# DE-230724.net
KiCad netlist of a schematic drawn in Altium Designer
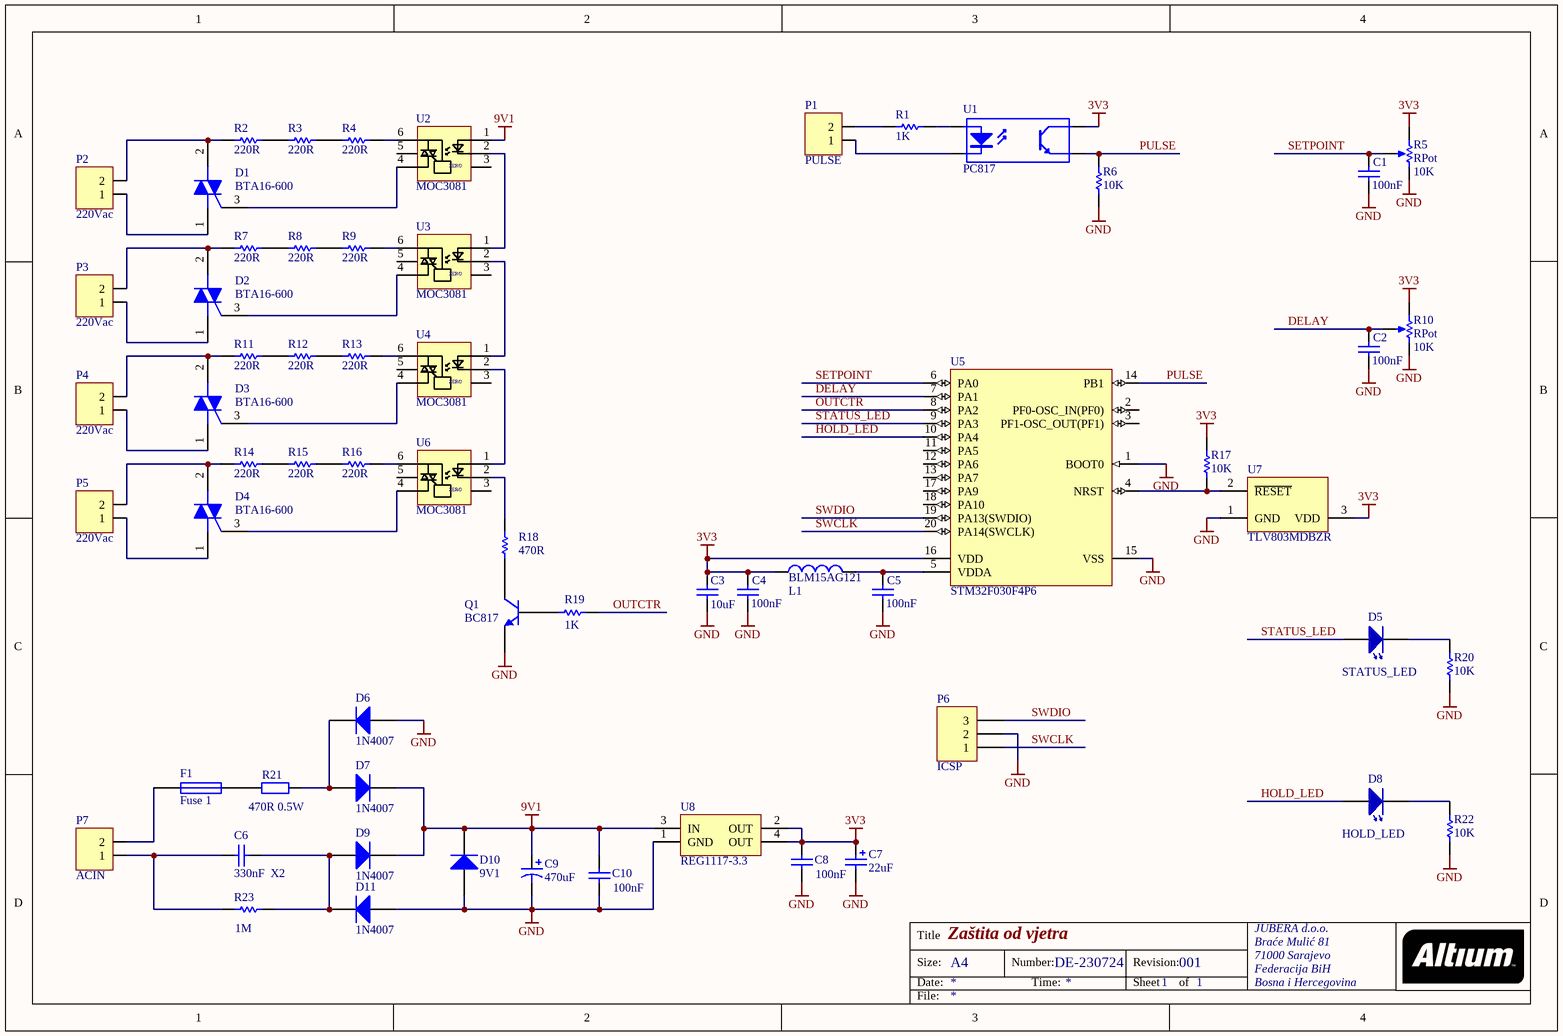
[diagram p0: DE-230724.SchDoc]

(export (version "E")
  (design (tool "Eeschema 10.0.6"))
  (components
    (comp (ref "C1")
      (value "100nF")
      (footprint "0603")
      (description "Ceramic Chip Capacitor - 25V")
      (fields (field (name "Comment") "C0603") (field (name "PUBLISHER") "Altium Limited"))
      (libsource (lib "DE-250624") (part "C0603"))
    )
    (comp (ref "C2")
      (value "100nF")
      (footprint "0603")
      (description "Ceramic Chip Capacitor - 25V")
      (fields (field (name "Comment") "C0603") (field (name "PUBLISHER") "Altium Limited"))
      (libsource (lib "DE-250624") (part "C0603"))
    )
    (comp (ref "C3")
      (value "10uF")
      (footprint "0805")
      (description "Ceramic Chip Capacitor - 25V")
      (fields (field (name "Comment") "C0805") (field (name "PUBLISHER") "Altium Limited"))
      (libsource (lib "DE-250624") (part "C0805"))
    )
    (comp (ref "C4")
      (value "100nF")
      (footprint "0603")
      (description "Ceramic Chip Capacitor - 25V")
      (fields (field (name "Comment") "C0603") (field (name "PUBLISHER") "Altium Limited"))
      (libsource (lib "DE-250624") (part "C0603"))
    )
    (comp (ref "C5")
      (value "100nF")
      (footprint "0603")
      (description "Ceramic Chip Capacitor - 25V")
      (fields (field (name "Comment") "C0603") (field (name "PUBLISHER") "Altium Limited"))
      (libsource (lib "DE-250624") (part "C0603"))
    )
    (comp (ref "C6")
      (value "330nF  X2")
      (footprint "0,33uF X2")
      (description "Dipped Radial Multilayer Ceramic Capacitor COG (NPO): 330nF 275VAC X2")
      (fields (field (name "PUBLISHER") "Altium Limited"))
      (libsource (lib "DE-230724") (part "0,33uF X2"))
    )
    (comp (ref "C7")
      (value "22uF")
      (footprint "CAPPR2-5X11")
      (description "Aluminum Electrolytic Capacitor, Radial Style with Long Leads: 47uF, 35V")
      (fields (field (name "PUBLISHER") "Altium Limited"))
      (libsource (lib "DE-230724") (part "EKA00AA247F00"))
    )
    (comp (ref "C8")
      (value "100nF")
      (footprint "0603")
      (description "Ceramic Chip Capacitor - Standard")
      (fields (field (name "Comment") "C0603") (field (name "PUBLISHER") "Altium Limited"))
      (libsource (lib "DE-230724") (part "C0603"))
    )
    (comp (ref "C9")
      (value "470uF")
      (footprint "CAPPR5-10X12.5")
      (description "Aluminum Electrolytic Capacitor, Radial Style with Long Leads: 470uF, 25V")
      (fields (field (name "PUBLISHER") "Altium Limited"))
      (libsource (lib "DE-230724") (part "EKA00DC347E00"))
    )
    (comp (ref "C10")
      (value "100nF")
      (footprint "0603")
      (description "Ceramic Chip Capacitor - Standard")
      (fields (field (name "Comment") "C0603") (field (name "PUBLISHER") "Altium Limited"))
      (libsource (lib "DE-230724") (part "C0603"))
    )
    (comp (ref "D1")
      (value "BTA16-600")
      (footprint "ONSC-TO-220-3-221A-07")
      (description "Triacs, Silicon Bidirectional Thyristor, 3-Pin TO-220, Pb-Free, Tube")
      (fields (field (name "MANUFACTURER") "On Semiconductor") (field (name "PARTNUMBER") "BTA08-600BW3G"))
      (libsource (lib "DE-100224") (part "BTA08-600BW3G"))
    )
    (comp (ref "D2")
      (value "BTA16-600")
      (footprint "ONSC-TO-220-3-221A-07")
      (description "Triacs, Silicon Bidirectional Thyristor, 3-Pin TO-220, Pb-Free, Tube")
      (fields (field (name "MANUFACTURER") "On Semiconductor") (field (name "PARTNUMBER") "BTA08-600BW3G"))
      (libsource (lib "DE-100224") (part "BTA08-600BW3G"))
    )
    (comp (ref "D3")
      (value "BTA16-600")
      (footprint "ONSC-TO-220-3-221A-07")
      (description "Triacs, Silicon Bidirectional Thyristor, 3-Pin TO-220, Pb-Free, Tube")
      (fields (field (name "MANUFACTURER") "On Semiconductor") (field (name "PARTNUMBER") "BTA08-600BW3G"))
      (libsource (lib "DE-100224") (part "BTA08-600BW3G"))
    )
    (comp (ref "D4")
      (value "BTA16-600")
      (footprint "ONSC-TO-220-3-221A-07")
      (description "Triacs, Silicon Bidirectional Thyristor, 3-Pin TO-220, Pb-Free, Tube")
      (fields (field (name "MANUFACTURER") "On Semiconductor") (field (name "PARTNUMBER") "BTA08-600BW3G"))
      (libsource (lib "DE-100224") (part "BTA08-600BW3G"))
    )
    (comp (ref "D5")
      (value "STATUS_LED")
      (footprint "LED 3mm")
      (libsource (lib "DE-230724") (part "LED 3mm"))
    )
    (comp (ref "D6")
      (value "1N4007")
      (footprint "SMB")
      (description "1 Amp General Purpose Rectifier")
      (fields (field (name "PUBLISHER") "Altium Limited"))
      (libsource (lib "Miscellaneous Devices") (part "Diode 1N4007"))
    )
    (comp (ref "D7")
      (value "1N4007")
      (footprint "SMB")
      (description "1 Amp General Purpose Rectifier")
      (fields (field (name "PUBLISHER") "Altium Limited"))
      (libsource (lib "Miscellaneous Devices") (part "Diode 1N4007"))
    )
    (comp (ref "D8") (value "HOLD_LED") (footprint "LED 3mm") (libsource (lib "DE-230724") (part "LED 3mm")))
    (comp (ref "D9")
      (value "1N4007")
      (footprint "SMB")
      (description "1 Amp General Purpose Rectifier")
      (fields (field (name "PUBLISHER") "Altium Limited"))
      (libsource (lib "Miscellaneous Devices") (part "Diode 1N4007"))
    )
    (comp (ref "D10")
      (value "9V1")
      (footprint "DO-41")
      (description "High Conductance Fast Diode")
      (fields (field (name "PUBLISHER") "Altium Limited"))
      (libsource (lib "DE-230724") (part "Diode 1N914"))
    )
    (comp (ref "D11")
      (value "1N4007")
      (footprint "SMB")
      (description "1 Amp General Purpose Rectifier")
      (fields (field (name "PUBLISHER") "Altium Limited"))
      (libsource (lib "Miscellaneous Devices") (part "Diode 1N4007"))
    )
    (comp (ref "F1")
      (value "Fuse 1")
      (footprint "PIN-W2/E2.8")
      (description "Fuse")
      (fields (field (name "PUBLISHER") "Altium Limited"))
      (libsource (lib "Miscellaneous Devices") (part "Fuse 1"))
    )
    (comp (ref "L1")
      (value "BLM15AG121")
      (footprint "0603")
      (description "Inductor")
      (fields (field (name "PUBLISHER") "Altium Limited"))
      (libsource (lib "DE-230724") (part "Inductor_SMD"))
    )
    (comp (ref "P1")
      (value "PULSE")
      (footprint "TERMINAL BLOK 2 - 7mm")
      (description "Terminal blok konektor 3,5 mm")
      (libsource (lib "DE-230724") (part "TERMINAL BLOK 2"))
    )
    (comp (ref "P2")
      (value "220Vac")
      (footprint "TERMINAL BLOK 2 - 3,5mm")
      (description "Terminal blok konektor 3,5 mm")
      (libsource (lib "DE-230724") (part "TERMINAL BLOK 2"))
    )
    (comp (ref "P3")
      (value "220Vac")
      (footprint "TERMINAL BLOK 2 - 3,5mm")
      (description "Terminal blok konektor 3,5 mm")
      (libsource (lib "DE-230724") (part "TERMINAL BLOK 2"))
    )
    (comp (ref "P4")
      (value "220Vac")
      (footprint "TERMINAL BLOK 2 - 3,5mm")
      (description "Terminal blok konektor 3,5 mm")
      (libsource (lib "DE-230724") (part "TERMINAL BLOK 2"))
    )
    (comp (ref "P5")
      (value "220Vac")
      (footprint "TERMINAL BLOK 2 - 3,5mm")
      (description "Terminal blok konektor 3,5 mm")
      (libsource (lib "DE-230724") (part "TERMINAL BLOK 2"))
    )
    (comp (ref "P6")
      (value "ICSP")
      (footprint "HDR1X3")
      (description "Header, 3-Pin")
      (fields (field (name "PUBLISHER") "Altium Limited"))
      (libsource (lib "Miscellaneous Connectors") (part "Header 3"))
    )
    (comp (ref "P7")
      (value "ACIN")
      (footprint "TERMINAL BLOK 2 - 7mm")
      (description "Terminal blok konektor 3,5 mm")
      (libsource (lib "DE-230724") (part "TERMINAL BLOK 2"))
    )
    (comp (ref "Q1")
      (value "BC817")
      (footprint "SOT23_N")
      (description "NPN General-purpose Transistor")
      (fields (field (name "PUBLISHER") "Altium Limited"))
      (libsource (lib "DE-230724") (part "BC817"))
    )
    (comp (ref "R1")
      (value "1K")
      (footprint "ERA-0603")
      (fields (field (name "PUBLISHER") "Altium Limited"))
      (libsource (lib "DE-230724") (part "ERAV"))
    )
    (comp (ref "R2")
      (value "220R")
      (footprint "ERA-0805")
      (fields (field (name "PUBLISHER") "Altium Limited"))
      (libsource (lib "DE-100224") (part "ERAS"))
    )
    (comp (ref "R3")
      (value "220R")
      (footprint "ERA-0805")
      (fields (field (name "PUBLISHER") "Altium Limited"))
      (libsource (lib "DE-100224") (part "ERAS"))
    )
    (comp (ref "R4")
      (value "220R")
      (footprint "ERA-0805")
      (fields (field (name "PUBLISHER") "Altium Limited"))
      (libsource (lib "DE-100224") (part "ERAS"))
    )
    (comp (ref "R5")
      (value "RPot")
      (footprint "HDR1X3")
      (description "Potentiometer")
      (fields (field (name "ALTIUM_VALUE") "10K") (field (name "PUBLISHER") "Altium Limited"))
      (libsource (lib "Miscellaneous Devices") (part "RPot"))
    )
    (comp (ref "R6")
      (value "10K")
      (footprint "ERA-0603")
      (fields (field (name "PUBLISHER") "Altium Limited"))
      (libsource (lib "DE-230724") (part "ERAV"))
    )
    (comp (ref "R7")
      (value "220R")
      (footprint "ERA-0805")
      (fields (field (name "PUBLISHER") "Altium Limited"))
      (libsource (lib "DE-100224") (part "ERAS"))
    )
    (comp (ref "R8")
      (value "220R")
      (footprint "ERA-0805")
      (fields (field (name "PUBLISHER") "Altium Limited"))
      (libsource (lib "DE-100224") (part "ERAS"))
    )
    (comp (ref "R9")
      (value "220R")
      (footprint "ERA-0805")
      (fields (field (name "PUBLISHER") "Altium Limited"))
      (libsource (lib "DE-100224") (part "ERAS"))
    )
    (comp (ref "R10")
      (value "RPot")
      (footprint "HDR1X3")
      (description "Potentiometer")
      (fields (field (name "ALTIUM_VALUE") "10K") (field (name "PUBLISHER") "Altium Limited"))
      (libsource (lib "Miscellaneous Devices") (part "RPot"))
    )
    (comp (ref "R11")
      (value "220R")
      (footprint "ERA-0805")
      (fields (field (name "PUBLISHER") "Altium Limited"))
      (libsource (lib "DE-100224") (part "ERAS"))
    )
    (comp (ref "R12")
      (value "220R")
      (footprint "ERA-0805")
      (fields (field (name "PUBLISHER") "Altium Limited"))
      (libsource (lib "DE-100224") (part "ERAS"))
    )
    (comp (ref "R13")
      (value "220R")
      (footprint "ERA-0805")
      (fields (field (name "PUBLISHER") "Altium Limited"))
      (libsource (lib "DE-100224") (part "ERAS"))
    )
    (comp (ref "R14")
      (value "220R")
      (footprint "ERA-0805")
      (fields (field (name "PUBLISHER") "Altium Limited"))
      (libsource (lib "DE-100224") (part "ERAS"))
    )
    (comp (ref "R15")
      (value "220R")
      (footprint "ERA-0805")
      (fields (field (name "PUBLISHER") "Altium Limited"))
      (libsource (lib "DE-100224") (part "ERAS"))
    )
    (comp (ref "R16")
      (value "220R")
      (footprint "ERA-0805")
      (fields (field (name "PUBLISHER") "Altium Limited"))
      (libsource (lib "DE-100224") (part "ERAS"))
    )
    (comp (ref "R17")
      (value "10K")
      (footprint "ERA-0603")
      (fields (field (name "PUBLISHER") "Altium Limited"))
      (libsource (lib "DE-230724") (part "ERAV"))
    )
    (comp (ref "R18")
      (value "470R")
      (footprint "ERA-0603")
      (fields (field (name "PUBLISHER") "Altium Limited"))
      (libsource (lib "DE-230724") (part "ERAV"))
    )
    (comp (ref "R19")
      (value "1K")
      (footprint "ERA-0603")
      (fields (field (name "PUBLISHER") "Altium Limited"))
      (libsource (lib "DE-230724") (part "ERAV"))
    )
    (comp (ref "R20")
      (value "10K")
      (footprint "ERA-0603")
      (fields (field (name "PUBLISHER") "Altium Limited"))
      (libsource (lib "DE-230724") (part "ERAV"))
    )
    (comp (ref "R21")
      (value "470R 0.5W")
      (footprint "AXIAL-0.4")
      (description "Resistor")
      (fields (field (name "Comment") "Res2") (field (name "PUBLISHER") "Altium Limited"))
      (libsource (lib "Miscellaneous Devices") (part "Res2"))
    )
    (comp (ref "R22")
      (value "10K")
      (footprint "ERA-0603")
      (fields (field (name "PUBLISHER") "Altium Limited"))
      (libsource (lib "DE-230724") (part "ERAV"))
    )
    (comp (ref "R23")
      (value "1M")
      (footprint "AXIAL-0.3")
      (description "Resistor")
      (fields (field (name "Comment") "Res1") (field (name "PUBLISHER") "Altium Limited"))
      (libsource (lib "Miscellaneous Devices") (part "Res1"))
    )
    (comp (ref "U1")
      (value "PC817")
      (footprint "DIP-4")
      (description "4-Pin Phototransistor Optocoupler")
      (fields (field (name "PUBLISHER") "Altium Limited"))
      (libsource (lib "DE-230724") (part "PC817"))
    )
    (comp (ref "U2")
      (value "MOC3081")
      (footprint "DIP6")
      (description "Zero-Cross Optoisolator Triac Driver")
      (libsource (lib "DE-100224") (part "MOC3081"))
    )
    (comp (ref "U3")
      (value "MOC3081")
      (footprint "DIP6")
      (description "Zero-Cross Optoisolator Triac Driver")
      (libsource (lib "DE-100224") (part "MOC3081"))
    )
    (comp (ref "U4")
      (value "MOC3081")
      (footprint "DIP6")
      (description "Zero-Cross Optoisolator Triac Driver")
      (libsource (lib "DE-100224") (part "MOC3081"))
    )
    (comp (ref "U5")
      (value "STM32F030F4P6")
      (footprint "STM-TSSOP20_N")
      (libsource (lib "STMicroelectronics STM32 F0") (part "STM32F030F4P6"))
    )
    (comp (ref "U6")
      (value "MOC3081")
      (footprint "DIP6")
      (description "Zero-Cross Optoisolator Triac Driver")
      (libsource (lib "DE-100224") (part "MOC3081"))
    )
    (comp (ref "U7")
      (value "TLV803MDBZR")
      (footprint "DBZ3_N")
      (fields (field (name "MANUFACTURER") "Texas Instruments"))
      (libsource (lib "TI Power Management Supervisor and Reset IC") (part "TLV803MDBZR"))
    )
    (comp (ref "U8")
      (value "REG1117-3.3")
      (footprint "ZZ311")
      (description "800mA and 1A Low Dropout Positive Regulator 2.85V, 3.3V, 5V, and Adjustable")
      (fields (field (name "PUBLISHER") "Altium Limited"))
      (libsource (lib "DE-230724") (part "REG1117-3.3"))
    )
  )
  (nets
    (net (code "1") (name "/DELAY") (class "Default")
      (node (ref "C2") (pin "2") (pinfunction "2_2") (pintype "passive"))
      (node (ref "R10") (pin "3") (pinfunction "TAP_3") (pintype "passive"))
      (node (ref "U5") (pin "7") (pinfunction "PA1_7") (pintype "bidirectional"))
    )
    (net (code "2") (name "/HOLD_LED") (class "Default")
      (node (ref "D8") (pin "2") (pinfunction "2_2") (pintype "passive"))
      (node (ref "U5") (pin "10") (pinfunction "PA4_10") (pintype "bidirectional"))
    )
    (net (code "3") (name "/OUTCTR") (class "Default")
      (node (ref "R19") (pin "1") (pinfunction "1_1") (pintype "passive"))
      (node (ref "U5") (pin "8") (pinfunction "PA2_8") (pintype "bidirectional"))
    )
    (net (code "4") (name "/PULSE") (class "Default")
      (node (ref "R6") (pin "1") (pinfunction "1_1") (pintype "passive"))
      (node (ref "U1") (pin "3") (pinfunction "E_3") (pintype "passive"))
      (node (ref "U5") (pin "14") (pinfunction "PB1_14") (pintype "bidirectional"))
    )
    (net (code "5") (name "/SETPOINT") (class "Default")
      (node (ref "C1") (pin "2") (pinfunction "2_2") (pintype "passive"))
      (node (ref "R5") (pin "3") (pinfunction "TAP_3") (pintype "passive"))
      (node (ref "U5") (pin "6") (pinfunction "PA0_6") (pintype "bidirectional"))
    )
    (net (code "6") (name "/STATUS_LED") (class "Default")
      (node (ref "D5") (pin "2") (pinfunction "2_2") (pintype "passive"))
      (node (ref "U5") (pin "9") (pinfunction "PA3_9") (pintype "bidirectional"))
    )
    (net (code "7") (name "/SWCLK") (class "Default")
      (node (ref "P6") (pin "1") (pinfunction "1_1") (pintype "passive"))
      (node (ref "U5") (pin "20") (pinfunction "PA14(SWCLK)_20") (pintype "bidirectional"))
    )
    (net (code "8") (name "/SWDIO") (class "Default")
      (node (ref "P6") (pin "3") (pinfunction "3_3") (pintype "passive"))
      (node (ref "U5") (pin "19") (pinfunction "PA13(SWDIO)_19") (pintype "bidirectional"))
    )
    (net (code "9") (name "3V3") (class "Default")
      (node (ref "C3") (pin "2") (pinfunction "2_2") (pintype "passive"))
      (node (ref "C4") (pin "2") (pinfunction "2_2") (pintype "passive"))
      (node (ref "C7") (pin "1") (pinfunction "1_1") (pintype "passive"))
      (node (ref "C8") (pin "2") (pinfunction "2_2") (pintype "passive"))
      (node (ref "L1") (pin "1") (pinfunction "1_1") (pintype "passive"))
      (node (ref "R10") (pin "1") (pinfunction "TOP_1") (pintype "passive"))
      (node (ref "R17") (pin "2") (pinfunction "2_2") (pintype "passive"))
      (node (ref "R5") (pin "1") (pinfunction "TOP_1") (pintype "passive"))
      (node (ref "U1") (pin "4") (pinfunction "C_4") (pintype "passive"))
      (node (ref "U5") (pin "16") (pinfunction "VDD_16") (pintype "power_in"))
      (node (ref "U7") (pin "3") (pinfunction "VDD_3") (pintype "power_in"))
      (node (ref "U8") (pin "2") (pinfunction "OUT_2") (pintype "power_in"))
      (node (ref "U8") (pin "4") (pinfunction "OUT_4") (pintype "power_in"))
    )
    (net (code "10") (name "9V1") (class "Default")
      (node (ref "C10") (pin "2") (pinfunction "2_2") (pintype "passive"))
      (node (ref "C9") (pin "1") (pinfunction "1_1") (pintype "passive"))
      (node (ref "D10") (pin "2") (pinfunction "K_2") (pintype "passive"))
      (node (ref "D7") (pin "2") (pinfunction "K_2") (pintype "passive"))
      (node (ref "D9") (pin "2") (pinfunction "K_2") (pintype "passive"))
      (node (ref "U2") (pin "1") (pinfunction "1_1") (pintype "passive"))
      (node (ref "U8") (pin "3") (pinfunction "IN_3") (pintype "power_in"))
    )
    (net (code "11") (name "GND") (class "Default")
      (node (ref "C1") (pin "1") (pinfunction "1_1") (pintype "passive"))
      (node (ref "C10") (pin "1") (pinfunction "1_1") (pintype "passive"))
      (node (ref "C2") (pin "1") (pinfunction "1_1") (pintype "passive"))
      (node (ref "C3") (pin "1") (pinfunction "1_1") (pintype "passive"))
      (node (ref "C4") (pin "1") (pinfunction "1_1") (pintype "passive"))
      (node (ref "C5") (pin "1") (pinfunction "1_1") (pintype "passive"))
      (node (ref "C7") (pin "2") (pinfunction "2_2") (pintype "passive"))
      (node (ref "C8") (pin "1") (pinfunction "1_1") (pintype "passive"))
      (node (ref "C9") (pin "2") (pinfunction "2_2") (pintype "passive"))
      (node (ref "D10") (pin "1") (pinfunction "A_1") (pintype "passive"))
      (node (ref "D11") (pin "1") (pinfunction "A_1") (pintype "passive"))
      (node (ref "D6") (pin "1") (pinfunction "A_1") (pintype "passive"))
      (node (ref "P6") (pin "2") (pinfunction "2_2") (pintype "passive"))
      (node (ref "Q1") (pin "2") (pinfunction "E_2") (pintype "passive"))
      (node (ref "R10") (pin "2") (pinfunction "BOT_2") (pintype "passive"))
      (node (ref "R20") (pin "2") (pinfunction "2_2") (pintype "passive"))
      (node (ref "R22") (pin "2") (pinfunction "2_2") (pintype "passive"))
      (node (ref "R5") (pin "2") (pinfunction "BOT_2") (pintype "passive"))
      (node (ref "R6") (pin "2") (pinfunction "2_2") (pintype "passive"))
      (node (ref "U5") (pin "1") (pinfunction "BOOT0_1") (pintype "input"))
      (node (ref "U5") (pin "15") (pinfunction "VSS_15") (pintype "power_in"))
      (node (ref "U7") (pin "1") (pinfunction "GND_1") (pintype "power_in"))
      (node (ref "U8") (pin "1") (pinfunction "GND_1") (pintype "power_in"))
    )
    (net (code "12") (name "Net-(C6-Pad1)") (class "Default")
      (node (ref "C6") (pin "1") (pinfunction "1_1") (pintype "passive"))
      (node (ref "P7") (pin "1") (pinfunction "1_1") (pintype "passive"))
      (node (ref "R23") (pin "1") (pinfunction "1_1") (pintype "passive"))
    )
    (net (code "13") (name "Net-(D1-G)") (class "Default")
      (node (ref "D1") (pin "3") (pinfunction "G_3") (pintype "passive"))
      (node (ref "U2") (pin "4") (pinfunction "4_4") (pintype "passive"))
    )
    (net (code "14") (name "Net-(D1-MT1)") (class "Default")
      (node (ref "D1") (pin "1") (pinfunction "MT1_1") (pintype "passive"))
      (node (ref "P2") (pin "1") (pinfunction "1_1") (pintype "passive"))
    )
    (net (code "15") (name "Net-(D1-MT2)") (class "Default")
      (node (ref "D1") (pin "2") (pinfunction "MT2_2") (pintype "passive"))
      (node (ref "P2") (pin "2") (pinfunction "2_2") (pintype "passive"))
      (node (ref "R2") (pin "1") (pinfunction "1_1") (pintype "passive"))
    )
    (net (code "16") (name "Net-(D2-G)") (class "Default")
      (node (ref "D2") (pin "3") (pinfunction "G_3") (pintype "passive"))
      (node (ref "U3") (pin "4") (pinfunction "4_4") (pintype "passive"))
    )
    (net (code "17") (name "Net-(D2-MT1)") (class "Default")
      (node (ref "D2") (pin "1") (pinfunction "MT1_1") (pintype "passive"))
      (node (ref "P3") (pin "1") (pinfunction "1_1") (pintype "passive"))
    )
    (net (code "18") (name "Net-(D2-MT2)") (class "Default")
      (node (ref "D2") (pin "2") (pinfunction "MT2_2") (pintype "passive"))
      (node (ref "P3") (pin "2") (pinfunction "2_2") (pintype "passive"))
      (node (ref "R7") (pin "1") (pinfunction "1_1") (pintype "passive"))
    )
    (net (code "19") (name "Net-(D3-G)") (class "Default")
      (node (ref "D3") (pin "3") (pinfunction "G_3") (pintype "passive"))
      (node (ref "U4") (pin "4") (pinfunction "4_4") (pintype "passive"))
    )
    (net (code "20") (name "Net-(D3-MT1)") (class "Default")
      (node (ref "D3") (pin "1") (pinfunction "MT1_1") (pintype "passive"))
      (node (ref "P4") (pin "1") (pinfunction "1_1") (pintype "passive"))
    )
    (net (code "21") (name "Net-(D3-MT2)") (class "Default")
      (node (ref "D3") (pin "2") (pinfunction "MT2_2") (pintype "passive"))
      (node (ref "P4") (pin "2") (pinfunction "2_2") (pintype "passive"))
      (node (ref "R11") (pin "1") (pinfunction "1_1") (pintype "passive"))
    )
    (net (code "22") (name "Net-(D4-G)") (class "Default")
      (node (ref "D4") (pin "3") (pinfunction "G_3") (pintype "passive"))
      (node (ref "U6") (pin "4") (pinfunction "4_4") (pintype "passive"))
    )
    (net (code "23") (name "Net-(D4-MT1)") (class "Default")
      (node (ref "D4") (pin "1") (pinfunction "MT1_1") (pintype "passive"))
      (node (ref "P5") (pin "1") (pinfunction "1_1") (pintype "passive"))
    )
    (net (code "24") (name "Net-(D4-MT2)") (class "Default")
      (node (ref "D4") (pin "2") (pinfunction "MT2_2") (pintype "passive"))
      (node (ref "P5") (pin "2") (pinfunction "2_2") (pintype "passive"))
      (node (ref "R14") (pin "1") (pinfunction "1_1") (pintype "passive"))
    )
    (net (code "25") (name "Net-(D5-Pad1)") (class "Default")
      (node (ref "D5") (pin "1") (pinfunction "1_1") (pintype "passive"))
      (node (ref "R20") (pin "1") (pinfunction "1_1") (pintype "passive"))
    )
    (net (code "26") (name "Net-(D6-K)") (class "Default")
      (node (ref "D6") (pin "2") (pinfunction "K_2") (pintype "passive"))
      (node (ref "D7") (pin "1") (pinfunction "A_1") (pintype "passive"))
      (node (ref "R21") (pin "2") (pinfunction "2_2") (pintype "passive"))
    )
    (net (code "27") (name "Net-(D8-Pad1)") (class "Default")
      (node (ref "D8") (pin "1") (pinfunction "1_1") (pintype "passive"))
      (node (ref "R22") (pin "1") (pinfunction "1_1") (pintype "passive"))
    )
    (net (code "28") (name "Net-(D11-K)") (class "Default")
      (node (ref "C6") (pin "2") (pinfunction "2_2") (pintype "passive"))
      (node (ref "D11") (pin "2") (pinfunction "K_2") (pintype "passive"))
      (node (ref "D9") (pin "1") (pinfunction "A_1") (pintype "passive"))
      (node (ref "R23") (pin "2") (pinfunction "2_2") (pintype "passive"))
    )
    (net (code "29") (name "Net-(F1-Pad1)") (class "Default")
      (node (ref "F1") (pin "1") (pinfunction "1_1") (pintype "passive"))
      (node (ref "P7") (pin "2") (pinfunction "2_2") (pintype "passive"))
    )
    (net (code "30") (name "Net-(F1-Pad2)") (class "Default")
      (node (ref "F1") (pin "2") (pinfunction "2_2") (pintype "passive"))
      (node (ref "R21") (pin "1") (pinfunction "1_1") (pintype "passive"))
    )
    (net (code "31") (name "Net-(P1-Pad2)") (class "Default")
      (node (ref "P1") (pin "2") (pinfunction "2_2") (pintype "passive"))
      (node (ref "R1") (pin "1") (pinfunction "1_1") (pintype "passive"))
    )
    (net (code "32") (name "Net-(Q1-B)") (class "Default")
      (node (ref "Q1") (pin "1") (pinfunction "B_1") (pintype "passive"))
      (node (ref "R19") (pin "2") (pinfunction "2_2") (pintype "passive"))
    )
    (net (code "33") (name "Net-(Q1-C)") (class "Default")
      (node (ref "Q1") (pin "3") (pinfunction "C_3") (pintype "passive"))
      (node (ref "R18") (pin "1") (pinfunction "1_1") (pintype "passive"))
    )
    (net (code "34") (name "Net-(R2-Pad2)") (class "Default")
      (node (ref "R2") (pin "2") (pinfunction "2_2") (pintype "passive"))
      (node (ref "R3") (pin "1") (pinfunction "1_1") (pintype "passive"))
    )
    (net (code "35") (name "Net-(R3-Pad2)") (class "Default")
      (node (ref "R3") (pin "2") (pinfunction "2_2") (pintype "passive"))
      (node (ref "R4") (pin "1") (pinfunction "1_1") (pintype "passive"))
    )
    (net (code "36") (name "Net-(R4-Pad2)") (class "Default")
      (node (ref "R4") (pin "2") (pinfunction "2_2") (pintype "passive"))
      (node (ref "U2") (pin "6") (pinfunction "6_6") (pintype "passive"))
    )
    (net (code "37") (name "Net-(R7-Pad2)") (class "Default")
      (node (ref "R7") (pin "2") (pinfunction "2_2") (pintype "passive"))
      (node (ref "R8") (pin "1") (pinfunction "1_1") (pintype "passive"))
    )
    (net (code "38") (name "Net-(R8-Pad2)") (class "Default")
      (node (ref "R8") (pin "2") (pinfunction "2_2") (pintype "passive"))
      (node (ref "R9") (pin "1") (pinfunction "1_1") (pintype "passive"))
    )
    (net (code "39") (name "Net-(R9-Pad2)") (class "Default")
      (node (ref "R9") (pin "2") (pinfunction "2_2") (pintype "passive"))
      (node (ref "U3") (pin "6") (pinfunction "6_6") (pintype "passive"))
    )
    (net (code "40") (name "Net-(R11-Pad2)") (class "Default")
      (node (ref "R11") (pin "2") (pinfunction "2_2") (pintype "passive"))
      (node (ref "R12") (pin "1") (pinfunction "1_1") (pintype "passive"))
    )
    (net (code "41") (name "Net-(R12-Pad2)") (class "Default")
      (node (ref "R12") (pin "2") (pinfunction "2_2") (pintype "passive"))
      (node (ref "R13") (pin "1") (pinfunction "1_1") (pintype "passive"))
    )
    (net (code "42") (name "Net-(R13-Pad2)") (class "Default")
      (node (ref "R13") (pin "2") (pinfunction "2_2") (pintype "passive"))
      (node (ref "U4") (pin "6") (pinfunction "6_6") (pintype "passive"))
    )
    (net (code "43") (name "Net-(R14-Pad2)") (class "Default")
      (node (ref "R14") (pin "2") (pinfunction "2_2") (pintype "passive"))
      (node (ref "R15") (pin "1") (pinfunction "1_1") (pintype "passive"))
    )
    (net (code "44") (name "Net-(R15-Pad2)") (class "Default")
      (node (ref "R15") (pin "2") (pinfunction "2_2") (pintype "passive"))
      (node (ref "R16") (pin "1") (pinfunction "1_1") (pintype "passive"))
    )
    (net (code "45") (name "Net-(R16-Pad2)") (class "Default")
      (node (ref "R16") (pin "2") (pinfunction "2_2") (pintype "passive"))
      (node (ref "U6") (pin "6") (pinfunction "6_6") (pintype "passive"))
    )
    (net (code "46") (name "Net-(R18-Pad2)") (class "Default")
      (node (ref "R18") (pin "2") (pinfunction "2_2") (pintype "passive"))
      (node (ref "U6") (pin "2") (pinfunction "2_2") (pintype "passive"))
    )
    (net (code "47") (name "Net-(U1-A)") (class "Default")
      (node (ref "R1") (pin "2") (pinfunction "2_2") (pintype "passive"))
      (node (ref "U1") (pin "1") (pinfunction "A_1") (pintype "passive"))
    )
    (net (code "48") (name "Net-(U1-K)") (class "Default")
      (node (ref "P1") (pin "1") (pinfunction "1_1") (pintype "passive"))
      (node (ref "U1") (pin "2") (pinfunction "K_2") (pintype "passive"))
    )
    (net (code "49") (name "Net-(U2-Pad2)") (class "Default")
      (node (ref "U2") (pin "2") (pinfunction "2_2") (pintype "passive"))
      (node (ref "U3") (pin "1") (pinfunction "1_1") (pintype "passive"))
    )
    (net (code "50") (name "Net-(U3-Pad2)") (class "Default")
      (node (ref "U3") (pin "2") (pinfunction "2_2") (pintype "passive"))
      (node (ref "U4") (pin "1") (pinfunction "1_1") (pintype "passive"))
    )
    (net (code "51") (name "Net-(U4-Pad2)") (class "Default")
      (node (ref "U4") (pin "2") (pinfunction "2_2") (pintype "passive"))
      (node (ref "U6") (pin "1") (pinfunction "1_1") (pintype "passive"))
    )
    (net (code "52") (name "Net-(U5-NRST)") (class "Default")
      (node (ref "R17") (pin "1") (pinfunction "1_1") (pintype "passive"))
      (node (ref "U5") (pin "4") (pinfunction "NRST_4") (pintype "bidirectional"))
      (node (ref "U7") (pin "2") (pinfunction "~{RESET}_2") (pintype "open_collector"))
    )
    (net (code "53") (name "Net-(U5-VDDA)") (class "Default")
      (node (ref "C5") (pin "2") (pinfunction "2_2") (pintype "passive"))
      (node (ref "L1") (pin "2") (pinfunction "2_2") (pintype "passive"))
      (node (ref "U5") (pin "5") (pinfunction "VDDA_5") (pintype "power_in"))
    )
    (net (code "54") (name "unconnected-(U2-Pad3)") (class "Default")
      (node (ref "U2") (pin "3") (pinfunction "3_3") (pintype "passive"))
    )
    (net (code "55") (name "unconnected-(U2-Pad5)") (class "Default")
      (node (ref "U2") (pin "5") (pinfunction "5_5") (pintype "passive"))
    )
    (net (code "56") (name "unconnected-(U3-Pad3)") (class "Default")
      (node (ref "U3") (pin "3") (pinfunction "3_3") (pintype "passive"))
    )
    (net (code "57") (name "unconnected-(U3-Pad5)") (class "Default")
      (node (ref "U3") (pin "5") (pinfunction "5_5") (pintype "passive"))
    )
    (net (code "58") (name "unconnected-(U4-Pad3)") (class "Default")
      (node (ref "U4") (pin "3") (pinfunction "3_3") (pintype "passive"))
    )
    (net (code "59") (name "unconnected-(U4-Pad5)") (class "Default")
      (node (ref "U4") (pin "5") (pinfunction "5_5") (pintype "passive"))
    )
    (net (code "60") (name "unconnected-(U5-PA5-Pad11)") (class "Default")
      (node (ref "U5") (pin "11") (pinfunction "PA5_11") (pintype "bidirectional"))
    )
    (net (code "61") (name "unconnected-(U5-PA6-Pad12)") (class "Default")
      (node (ref "U5") (pin "12") (pinfunction "PA6_12") (pintype "bidirectional"))
    )
    (net (code "62") (name "unconnected-(U5-PA7-Pad13)") (class "Default")
      (node (ref "U5") (pin "13") (pinfunction "PA7_13") (pintype "bidirectional"))
    )
    (net (code "63") (name "unconnected-(U5-PA9-Pad17)") (class "Default")
      (node (ref "U5") (pin "17") (pinfunction "PA9_17") (pintype "bidirectional"))
    )
    (net (code "64") (name "unconnected-(U5-PA10-Pad18)") (class "Default")
      (node (ref "U5") (pin "18") (pinfunction "PA10_18") (pintype "bidirectional"))
    )
    (net (code "65") (name "unconnected-(U5-PF0-OSC_IN(PF0)-Pad2)") (class "Default")
      (node (ref "U5") (pin "2") (pinfunction "PF0-OSC_IN(PF0)_2") (pintype "bidirectional"))
    )
    (net (code "66") (name "unconnected-(U5-PF1-OSC_OUT(PF1)-Pad3)") (class "Default")
      (node (ref "U5") (pin "3") (pinfunction "PF1-OSC_OUT(PF1)_3") (pintype "bidirectional"))
    )
    (net (code "67") (name "unconnected-(U6-Pad3)") (class "Default")
      (node (ref "U6") (pin "3") (pinfunction "3_3") (pintype "passive"))
    )
    (net (code "68") (name "unconnected-(U6-Pad5)") (class "Default")
      (node (ref "U6") (pin "5") (pinfunction "5_5") (pintype "passive"))
    )
  )
)
